# pocsagboardv2.net
KiCad netlist of a schematic drawn in EAGLE
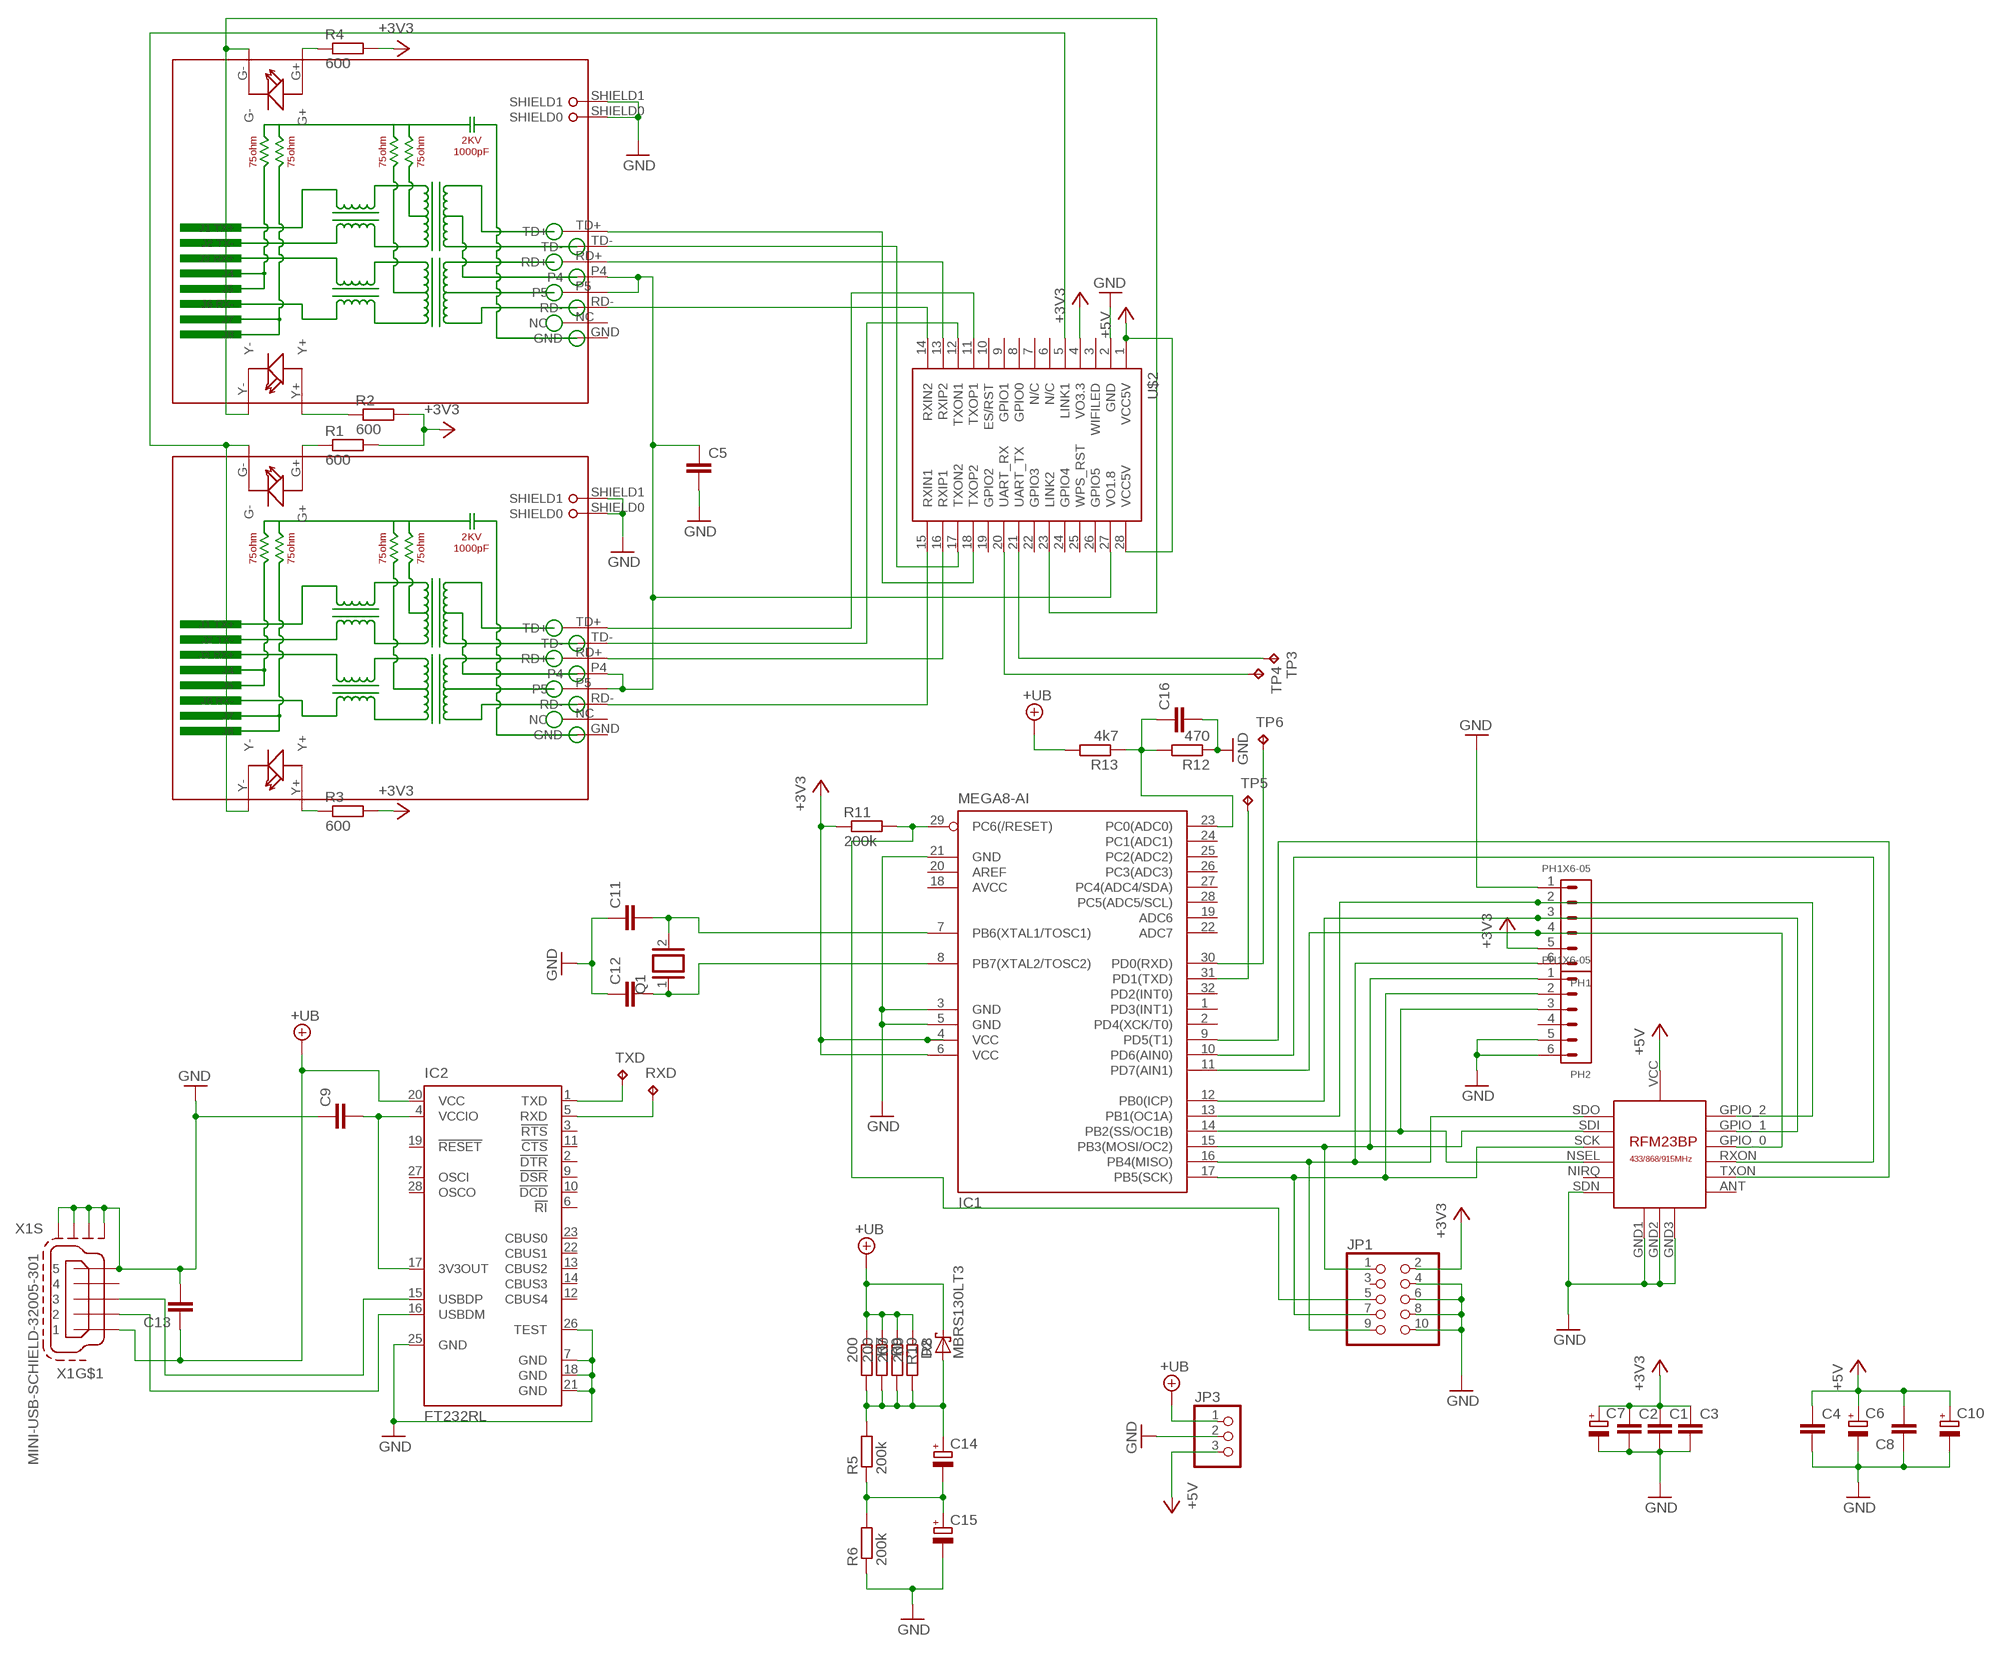
[diagram p0: schematic, sheet 1]

(export (version "E")
  (design (tool "Eeschema 10.0.6"))
  (components
    (comp (ref "C1")
      (value "C-EUC1206K")
      (footprint "eagle-import:C1206K")
      (libsource (lib "eagle-import") (part "C-EUC1206K"))
    )
    (comp (ref "C2")
      (value "C-EUC1206K")
      (footprint "eagle-import:C1206K")
      (libsource (lib "eagle-import") (part "C-EUC1206K"))
    )
    (comp (ref "C3")
      (value "C-EUC1206K")
      (footprint "eagle-import:C1206K")
      (libsource (lib "eagle-import") (part "C-EUC1206K"))
    )
    (comp (ref "C4")
      (value "C-EUC1206K")
      (footprint "eagle-import:C1206K")
      (libsource (lib "eagle-import") (part "C-EUC1206K"))
    )
    (comp (ref "C5")
      (value "C-EUC1206K")
      (footprint "eagle-import:C1206K")
      (libsource (lib "eagle-import") (part "C-EUC1206K"))
    )
    (comp (ref "C6")
      (value "CPOL-EU175TMP-0808")
      (footprint "eagle-import:175TMP-0808")
      (libsource (lib "eagle-import") (part "CPOL-EU175TMP-0808"))
    )
    (comp (ref "C7")
      (value "CPOL-EU175TMP-0808")
      (footprint "eagle-import:175TMP-0808")
      (libsource (lib "eagle-import") (part "CPOL-EU175TMP-0808"))
    )
    (comp (ref "C8")
      (value "C-EUC1206K")
      (footprint "eagle-import:C1206K")
      (libsource (lib "eagle-import") (part "C-EUC1206K"))
    )
    (comp (ref "C9")
      (value "C-EUC1206K")
      (footprint "eagle-import:C1206K")
      (libsource (lib "eagle-import") (part "C-EUC1206K"))
    )
    (comp (ref "C10")
      (value "CPOL-EU175TMP-0808")
      (footprint "eagle-import:175TMP-0808")
      (libsource (lib "eagle-import") (part "CPOL-EU175TMP-0808"))
    )
    (comp (ref "C11")
      (value "C-EUC0805")
      (footprint "eagle-import:C0805")
      (libsource (lib "eagle-import") (part "C-EUC0805"))
    )
    (comp (ref "C12")
      (value "C-EUC0805")
      (footprint "eagle-import:C0805")
      (libsource (lib "eagle-import") (part "C-EUC0805"))
    )
    (comp (ref "C13")
      (value "C-EUC1206K")
      (footprint "eagle-import:C1206K")
      (libsource (lib "eagle-import") (part "C-EUC1206K"))
    )
    (comp (ref "C14")
      (value "CPOL-EUSANYO_F")
      (footprint "eagle-import:SANYO-OSCON_F")
      (libsource (lib "eagle-import") (part "CPOL-EUSANYO_F"))
    )
    (comp (ref "C15")
      (value "CPOL-EUSANYO_F")
      (footprint "eagle-import:SANYO-OSCON_F")
      (libsource (lib "eagle-import") (part "CPOL-EUSANYO_F"))
    )
    (comp (ref "C16")
      (value "C-EUC1206K")
      (footprint "eagle-import:C1206K")
      (libsource (lib "eagle-import") (part "C-EUC1206K"))
    )
    (comp (ref "D2")
      (value "MBRS130LT3")
      (footprint "eagle-import:SMB")
      (libsource (lib "eagle-import") (part "MBRS130LT3"))
    )
    (comp (ref "IC1")
      (value "MEGA8-AI")
      (footprint "eagle-import:TQFP32-08")
      (fields (field (name "MPN") "ATMEGA8-16AU"))
      (libsource (lib "eagle-import") (part "MEGA8-AI"))
    )
    (comp (ref "IC2")
      (value "FT232RL")
      (footprint "eagle-import:SSOP28")
      (libsource (lib "eagle-import") (part "FT232RL"))
    )
    (comp (ref "JP1")
      (value "PINHD-2X5")
      (footprint "eagle-import:2X05")
      (libsource (lib "eagle-import") (part "PINHD-2X5"))
    )
    (comp (ref "JP3")
      (value "PINHD-1X3")
      (footprint "eagle-import:1X03")
      (libsource (lib "eagle-import") (part "PINHD-1X3"))
    )
    (comp (ref "PH1")
      (value "PH1X6-05")
      (footprint "eagle-import:PH005-1-6")
      (libsource (lib "eagle-import") (part "PH1X6-05"))
    )
    (comp (ref "PH2")
      (value "PH1X6-05")
      (footprint "eagle-import:PH005-1-6")
      (libsource (lib "eagle-import") (part "PH1X6-05"))
    )
    (comp (ref "Q1")
      (value "XTAL/S")
      (footprint "eagle-import:QS")
      (libsource (lib "eagle-import") (part "XTAL/S"))
    )
    (comp (ref "R1")
      (value "600")
      (footprint "eagle-import:M1206")
      (libsource (lib "eagle-import") (part "R-EU_M1206"))
    )
    (comp (ref "R2")
      (value "600")
      (footprint "eagle-import:M1206")
      (libsource (lib "eagle-import") (part "R-EU_M1206"))
    )
    (comp (ref "R3")
      (value "600")
      (footprint "eagle-import:M1206")
      (libsource (lib "eagle-import") (part "R-EU_M1206"))
    )
    (comp (ref "R4")
      (value "600")
      (footprint "eagle-import:M1206")
      (libsource (lib "eagle-import") (part "R-EU_M1206"))
    )
    (comp (ref "R5")
      (value "200k")
      (footprint "eagle-import:R1206")
      (libsource (lib "eagle-import") (part "R-EU_R1206"))
    )
    (comp (ref "R6")
      (value "200k")
      (footprint "eagle-import:R1206")
      (libsource (lib "eagle-import") (part "R-EU_R1206"))
    )
    (comp (ref "R7")
      (value "200")
      (footprint "eagle-import:R1206")
      (libsource (lib "eagle-import") (part "R-EU_R1206"))
    )
    (comp (ref "R8")
      (value "200")
      (footprint "eagle-import:R1206")
      (libsource (lib "eagle-import") (part "R-EU_R1206"))
    )
    (comp (ref "R9")
      (value "200")
      (footprint "eagle-import:R1206")
      (libsource (lib "eagle-import") (part "R-EU_R1206"))
    )
    (comp (ref "R10")
      (value "200")
      (footprint "eagle-import:R1206")
      (libsource (lib "eagle-import") (part "R-EU_R1206"))
    )
    (comp (ref "R11")
      (value "200k")
      (footprint "eagle-import:R1206")
      (libsource (lib "eagle-import") (part "R-EU_R1206"))
    )
    (comp (ref "R12")
      (value "470")
      (footprint "eagle-import:R1206")
      (libsource (lib "eagle-import") (part "R-EU_R1206"))
    )
    (comp (ref "R13")
      (value "4k7")
      (footprint "eagle-import:R1206")
      (libsource (lib "eagle-import") (part "R-EU_R1206"))
    )
    (comp (ref "RJ1")
      (value "HR911105A")
      (footprint "eagle-import:HR911105A")
      (libsource (lib "eagle-import") (part "HR911105A"))
    )
    (comp (ref "RJ2")
      (value "HR911105A")
      (footprint "eagle-import:HR911105A")
      (libsource (lib "eagle-import") (part "HR911105A"))
    )
    (comp (ref "RXD")
      (value "TPTP10SQ")
      (footprint "eagle-import:TP10SQ")
      (libsource (lib "eagle-import") (part "TPTP10SQ"))
    )
    (comp (ref "TP3")
      (value "TPTP10SQ")
      (footprint "eagle-import:TP10SQ")
      (libsource (lib "eagle-import") (part "TPTP10SQ"))
    )
    (comp (ref "TP4")
      (value "TPTP10SQ")
      (footprint "eagle-import:TP10SQ")
      (libsource (lib "eagle-import") (part "TPTP10SQ"))
    )
    (comp (ref "TP5")
      (value "TPTP10SQ")
      (footprint "eagle-import:TP10SQ")
      (libsource (lib "eagle-import") (part "TPTP10SQ"))
    )
    (comp (ref "TP6")
      (value "TPTP10SQ")
      (footprint "eagle-import:TP10SQ")
      (libsource (lib "eagle-import") (part "TPTP10SQ"))
    )
    (comp (ref "TXD")
      (value "TPTP10SQ")
      (footprint "eagle-import:TP10SQ")
      (libsource (lib "eagle-import") (part "TPTP10SQ"))
    )
    (comp (ref "U$1")
      (value "RFM23BP")
      (footprint "eagle-import:RFM23BP")
      (libsource (lib "eagle-import") (part "RFM23BP"))
    )
    (comp (ref "U$2")
      (value "HLK-RM04")
      (footprint "eagle-import:HLK-RM04")
      (libsource (lib "eagle-import") (part "HLK-RM04"))
    )
    (comp (ref "X1")
      (value "MINI-USB-SCHIELD-32005-301")
      (footprint "eagle-import:32005-301")
      (libsource (lib "eagle-import") (part "MINI-USB-SCHIELD-32005-301"))
    )
  )
  (nets
    (net (code "1") (name "+3V3") (class "Default")
      (node (ref "C1") (pin "1") (pinfunction "1_1") (pintype "passive"))
      (node (ref "C2") (pin "1") (pinfunction "1_1") (pintype "passive"))
      (node (ref "C3") (pin "1") (pinfunction "1_1") (pintype "passive"))
      (node (ref "C7") (pin "+") (pinfunction "+_+") (pintype "passive"))
      (node (ref "IC1") (pin "4") (pinfunction "VCC_4") (pintype "power_in"))
      (node (ref "IC1") (pin "6") (pinfunction "VCC_6") (pintype "power_in"))
      (node (ref "JP1") (pin "2") (pinfunction "2_2") (pintype "passive"))
      (node (ref "PH1") (pin "5") (pinfunction "5_5") (pintype "bidirectional"))
      (node (ref "R1") (pin "2") (pinfunction "2_2") (pintype "passive"))
      (node (ref "R11") (pin "1") (pinfunction "1_1") (pintype "passive"))
      (node (ref "R2") (pin "2") (pinfunction "2_2") (pintype "passive"))
      (node (ref "R3") (pin "2") (pinfunction "2_2") (pintype "passive"))
      (node (ref "R4") (pin "2") (pinfunction "2_2") (pintype "passive"))
      (node (ref "U$2") (pin "4") (pinfunction "VO3.3_4") (pintype "bidirectional"))
    )
    (net (code "2") (name "+5V") (class "Default")
      (node (ref "C10") (pin "+") (pinfunction "+_+") (pintype "passive"))
      (node (ref "C4") (pin "1") (pinfunction "1_1") (pintype "passive"))
      (node (ref "C6") (pin "+") (pinfunction "+_+") (pintype "passive"))
      (node (ref "C8") (pin "2") (pinfunction "2_2") (pintype "passive"))
      (node (ref "JP3") (pin "3") (pinfunction "3_3") (pintype "passive"))
      (node (ref "U$1") (pin "VCC") (pinfunction "VCC_VCC") (pintype "power_in"))
      (node (ref "U$2") (pin "1") (pinfunction "VCC5V_1") (pintype "bidirectional"))
      (node (ref "U$2") (pin "28") (pinfunction "VCC5V_28") (pintype "bidirectional"))
    )
    (net (code "3") (name "+UB") (class "Default")
      (node (ref "C13") (pin "1") (pinfunction "1_1") (pintype "passive"))
      (node (ref "D2") (pin "C") (pinfunction "C_C") (pintype "passive"))
      (node (ref "IC2") (pin "20") (pinfunction "VCC_20") (pintype "power_in"))
      (node (ref "JP3") (pin "1") (pinfunction "1_1") (pintype "passive"))
      (node (ref "R10") (pin "1") (pinfunction "1_1") (pintype "passive"))
      (node (ref "R13") (pin "2") (pinfunction "2_2") (pintype "passive"))
      (node (ref "R7") (pin "1") (pinfunction "1_1") (pintype "passive"))
      (node (ref "R8") (pin "1") (pinfunction "1_1") (pintype "passive"))
      (node (ref "R9") (pin "1") (pinfunction "1_1") (pintype "passive"))
      (node (ref "X1") (pin "1") (pinfunction "1_1") (pintype "passive"))
    )
    (net (code "4") (name "/AVCC") (class "Default")
      (node (ref "IC1") (pin "18") (pinfunction "AVCC_18") (pintype "power_in"))
    )
    (net (code "5") (name "GND") (class "Default")
      (node (ref "C1") (pin "2") (pinfunction "2_2") (pintype "passive"))
      (node (ref "C10") (pin "-") (pinfunction "-_-") (pintype "passive"))
      (node (ref "C11") (pin "1") (pinfunction "1_1") (pintype "passive"))
      (node (ref "C12") (pin "1") (pinfunction "1_1") (pintype "passive"))
      (node (ref "C13") (pin "2") (pinfunction "2_2") (pintype "passive"))
      (node (ref "C15") (pin "-") (pinfunction "-_-") (pintype "passive"))
      (node (ref "C16") (pin "2") (pinfunction "2_2") (pintype "passive"))
      (node (ref "C2") (pin "2") (pinfunction "2_2") (pintype "passive"))
      (node (ref "C3") (pin "2") (pinfunction "2_2") (pintype "passive"))
      (node (ref "C4") (pin "2") (pinfunction "2_2") (pintype "passive"))
      (node (ref "C5") (pin "2") (pinfunction "2_2") (pintype "passive"))
      (node (ref "C6") (pin "-") (pinfunction "-_-") (pintype "passive"))
      (node (ref "C7") (pin "-") (pinfunction "-_-") (pintype "passive"))
      (node (ref "C8") (pin "1") (pinfunction "1_1") (pintype "passive"))
      (node (ref "C9") (pin "1") (pinfunction "1_1") (pintype "passive"))
      (node (ref "IC1") (pin "21") (pinfunction "GND_21") (pintype "power_in"))
      (node (ref "IC1") (pin "3") (pinfunction "GND_3") (pintype "power_in"))
      (node (ref "IC1") (pin "5") (pinfunction "GND_5") (pintype "power_in"))
      (node (ref "IC2") (pin "18") (pinfunction "GND_18") (pintype "power_in"))
      (node (ref "IC2") (pin "21") (pinfunction "GND_21") (pintype "power_in"))
      (node (ref "IC2") (pin "25") (pinfunction "GND_25") (pintype "power_in"))
      (node (ref "IC2") (pin "26") (pinfunction "TEST_26") (pintype "input"))
      (node (ref "IC2") (pin "7") (pinfunction "GND_7") (pintype "power_in"))
      (node (ref "JP1") (pin "10") (pinfunction "10_10") (pintype "passive"))
      (node (ref "JP1") (pin "4") (pinfunction "4_4") (pintype "passive"))
      (node (ref "JP1") (pin "6") (pinfunction "6_6") (pintype "passive"))
      (node (ref "JP1") (pin "8") (pinfunction "8_8") (pintype "passive"))
      (node (ref "JP3") (pin "2") (pinfunction "2_2") (pintype "passive"))
      (node (ref "PH1") (pin "1") (pinfunction "1_1") (pintype "bidirectional"))
      (node (ref "PH2") (pin "5") (pinfunction "5_5") (pintype "bidirectional"))
      (node (ref "PH2") (pin "6") (pinfunction "6_6") (pintype "bidirectional"))
      (node (ref "R12") (pin "1") (pinfunction "1_1") (pintype "passive"))
      (node (ref "R6") (pin "1") (pinfunction "1_1") (pintype "passive"))
      (node (ref "RJ1") (pin "SHIELD0") (pinfunction "SHIELD0_SHIELD0") (pintype "bidirectional"))
      (node (ref "RJ1") (pin "SHIELD1") (pinfunction "SHIELD1_SHIELD1") (pintype "bidirectional"))
      (node (ref "RJ2") (pin "SHIELD0") (pinfunction "SHIELD0_SHIELD0") (pintype "bidirectional"))
      (node (ref "RJ2") (pin "SHIELD1") (pinfunction "SHIELD1_SHIELD1") (pintype "bidirectional"))
      (node (ref "U$1") (pin "GND1") (pinfunction "GND1_GND1") (pintype "power_in"))
      (node (ref "U$1") (pin "GND2") (pinfunction "GND2_GND2") (pintype "power_in"))
      (node (ref "U$1") (pin "GND3") (pinfunction "GND3_GND3") (pintype "power_in"))
      (node (ref "U$1") (pin "SDN") (pinfunction "SDN_SDN") (pintype "bidirectional"))
      (node (ref "U$2") (pin "2") (pinfunction "GND_2") (pintype "bidirectional"))
      (node (ref "X1") (pin "5") (pinfunction "5_5") (pintype "passive"))
      (node (ref "X1") (pin "M1") (pinfunction "S1_M1") (pintype "passive"))
      (node (ref "X1") (pin "M2") (pinfunction "S2_M2") (pintype "passive"))
      (node (ref "X1") (pin "M3") (pinfunction "S3_M3") (pintype "passive"))
      (node (ref "X1") (pin "M4") (pinfunction "S4_M4") (pintype "passive"))
    )
    (net (code "6") (name "Net-(C14-Pad+)") (class "Default")
      (node (ref "C14") (pin "+") (pinfunction "+_+") (pintype "passive"))
      (node (ref "D2") (pin "A") (pinfunction "A_A") (pintype "passive"))
      (node (ref "R10") (pin "2") (pinfunction "2_2") (pintype "passive"))
      (node (ref "R5") (pin "2") (pinfunction "2_2") (pintype "passive"))
      (node (ref "R7") (pin "2") (pinfunction "2_2") (pintype "passive"))
      (node (ref "R8") (pin "2") (pinfunction "2_2") (pintype "passive"))
      (node (ref "R9") (pin "2") (pinfunction "2_2") (pintype "passive"))
    )
    (net (code "7") (name "Net-(C14-Pad-)") (class "Default")
      (node (ref "C14") (pin "-") (pinfunction "-_-") (pintype "passive"))
      (node (ref "C15") (pin "+") (pinfunction "+_+") (pintype "passive"))
      (node (ref "R5") (pin "1") (pinfunction "1_1") (pintype "passive"))
      (node (ref "R6") (pin "2") (pinfunction "2_2") (pintype "passive"))
    )
    (net (code "8") (name "Net-(IC1-PB0(ICP))") (class "Default")
      (node (ref "IC1") (pin "12") (pinfunction "PB0(ICP)_12") (pintype "bidirectional"))
      (node (ref "PH1") (pin "3") (pinfunction "3_3") (pintype "bidirectional"))
      (node (ref "U$1") (pin "GPIO_1") (pinfunction "GPIO_1_GPIO_1") (pintype "bidirectional"))
    )
    (net (code "9") (name "Net-(IC1-PB1(OC1A))") (class "Default")
      (node (ref "IC1") (pin "13") (pinfunction "PB1(OC1A)_13") (pintype "bidirectional"))
      (node (ref "PH1") (pin "2") (pinfunction "2_2") (pintype "bidirectional"))
      (node (ref "U$1") (pin "GPIO_2") (pinfunction "GPIO_2_GPIO_2") (pintype "bidirectional"))
    )
    (net (code "10") (name "Net-(IC1-PB2(SS{slash}OC1B))") (class "Default")
      (node (ref "IC1") (pin "14") (pinfunction "PB2(SS/OC1B)_14") (pintype "bidirectional"))
      (node (ref "PH2") (pin "3") (pinfunction "3_3") (pintype "bidirectional"))
      (node (ref "U$1") (pin "NSEL") (pinfunction "NSEL_NSEL") (pintype "bidirectional"))
    )
    (net (code "11") (name "Net-(IC1-PB3(MOSI{slash}OC2))") (class "Default")
      (node (ref "IC1") (pin "15") (pinfunction "PB3(MOSI/OC2)_15") (pintype "bidirectional"))
      (node (ref "JP1") (pin "1") (pinfunction "1_1") (pintype "passive"))
      (node (ref "PH2") (pin "1") (pinfunction "1_1") (pintype "bidirectional"))
      (node (ref "U$1") (pin "SDI") (pinfunction "SDI_SDI") (pintype "bidirectional"))
    )
    (net (code "12") (name "Net-(IC1-PB4(MISO))") (class "Default")
      (node (ref "IC1") (pin "16") (pinfunction "PB4(MISO)_16") (pintype "bidirectional"))
      (node (ref "JP1") (pin "9") (pinfunction "9_9") (pintype "passive"))
      (node (ref "PH1") (pin "6") (pinfunction "6_6") (pintype "bidirectional"))
      (node (ref "U$1") (pin "SDO") (pinfunction "SDO_SDO") (pintype "bidirectional"))
    )
    (net (code "13") (name "Net-(IC1-PB5(SCK))") (class "Default")
      (node (ref "IC1") (pin "17") (pinfunction "PB5(SCK)_17") (pintype "bidirectional"))
      (node (ref "JP1") (pin "7") (pinfunction "7_7") (pintype "passive"))
      (node (ref "PH2") (pin "2") (pinfunction "2_2") (pintype "bidirectional"))
      (node (ref "U$1") (pin "SCK") (pinfunction "SCK_SCK") (pintype "bidirectional"))
    )
    (net (code "14") (name "Net-(IC1-PB6(XTAL1{slash}TOSC1))") (class "Default")
      (node (ref "C11") (pin "2") (pinfunction "2_2") (pintype "passive"))
      (node (ref "IC1") (pin "7") (pinfunction "PB6(XTAL1/TOSC1)_7") (pintype "bidirectional"))
      (node (ref "Q1") (pin "2") (pinfunction "2_2") (pintype "passive"))
    )
    (net (code "15") (name "Net-(IC1-PB7(XTAL2{slash}TOSC2))") (class "Default")
      (node (ref "C12") (pin "2") (pinfunction "2_2") (pintype "passive"))
      (node (ref "IC1") (pin "8") (pinfunction "PB7(XTAL2/TOSC2)_8") (pintype "bidirectional"))
      (node (ref "Q1") (pin "1") (pinfunction "1_1") (pintype "passive"))
    )
    (net (code "16") (name "Net-(IC1-PC0(ADC0))") (class "Default")
      (node (ref "C16") (pin "1") (pinfunction "1_1") (pintype "passive"))
      (node (ref "IC1") (pin "23") (pinfunction "PC0(ADC0)_23") (pintype "bidirectional"))
      (node (ref "R12") (pin "2") (pinfunction "2_2") (pintype "passive"))
      (node (ref "R13") (pin "1") (pinfunction "1_1") (pintype "passive"))
    )
    (net (code "17") (name "Net-(IC1-PC6({slash}RESET))") (class "Default")
      (node (ref "IC1") (pin "29") (pinfunction "PC6(/RESET)_29") (pintype "bidirectional"))
      (node (ref "JP1") (pin "5") (pinfunction "5_5") (pintype "passive"))
      (node (ref "R11") (pin "2") (pinfunction "2_2") (pintype "passive"))
    )
    (net (code "18") (name "Net-(IC1-PD0(RXD))") (class "Default")
      (node (ref "IC1") (pin "30") (pinfunction "PD0(RXD)_30") (pintype "bidirectional"))
      (node (ref "TP6") (pin "TP") (pinfunction "TP_TP") (pintype "input"))
    )
    (net (code "19") (name "Net-(IC1-PD1(TXD))") (class "Default")
      (node (ref "IC1") (pin "31") (pinfunction "PD1(TXD)_31") (pintype "bidirectional"))
      (node (ref "TP5") (pin "TP") (pinfunction "TP_TP") (pintype "input"))
    )
    (net (code "20") (name "Net-(IC1-PD5(T1))") (class "Default")
      (node (ref "IC1") (pin "9") (pinfunction "PD5(T1)_9") (pintype "bidirectional"))
      (node (ref "U$1") (pin "TXON") (pinfunction "TXON_TXON") (pintype "bidirectional"))
    )
    (net (code "21") (name "Net-(IC1-PD6(AIN0))") (class "Default")
      (node (ref "IC1") (pin "10") (pinfunction "PD6(AIN0)_10") (pintype "bidirectional"))
      (node (ref "U$1") (pin "RXON") (pinfunction "RXON_RXON") (pintype "bidirectional"))
    )
    (net (code "22") (name "Net-(IC1-PD7(AIN1))") (class "Default")
      (node (ref "IC1") (pin "11") (pinfunction "PD7(AIN1)_11") (pintype "bidirectional"))
      (node (ref "PH1") (pin "4") (pinfunction "4_4") (pintype "bidirectional"))
      (node (ref "U$1") (pin "GPIO_0") (pinfunction "GPIO_0_GPIO_0") (pintype "bidirectional"))
    )
    (net (code "23") (name "Net-(IC2-3V3OUT)") (class "Default")
      (node (ref "C9") (pin "2") (pinfunction "2_2") (pintype "passive"))
      (node (ref "IC2") (pin "17") (pinfunction "3V3OUT_17") (pintype "output"))
      (node (ref "IC2") (pin "4") (pinfunction "VCCIO_4") (pintype "power_in"))
    )
    (net (code "24") (name "Net-(IC2-RXD)") (class "Default")
      (node (ref "IC2") (pin "5") (pinfunction "RXD_5") (pintype "input"))
      (node (ref "RXD") (pin "TP") (pinfunction "TP_TP") (pintype "input"))
    )
    (net (code "25") (name "Net-(IC2-TXD)") (class "Default")
      (node (ref "IC2") (pin "1") (pinfunction "TXD_1") (pintype "output"))
      (node (ref "TXD") (pin "TP") (pinfunction "TP_TP") (pintype "input"))
    )
    (net (code "26") (name "Net-(IC2-USBDM)") (class "Default")
      (node (ref "IC2") (pin "16") (pinfunction "USBDM_16") (pintype "bidirectional"))
      (node (ref "X1") (pin "2") (pinfunction "2_2") (pintype "passive"))
    )
    (net (code "27") (name "Net-(IC2-USBDP)") (class "Default")
      (node (ref "IC2") (pin "15") (pinfunction "USBDP_15") (pintype "bidirectional"))
      (node (ref "X1") (pin "3") (pinfunction "3_3") (pintype "passive"))
    )
    (net (code "28") (name "Net-(R1-Pad1)") (class "Default")
      (node (ref "R1") (pin "1") (pinfunction "1_1") (pintype "passive"))
      (node (ref "RJ1") (pin "G+") (pinfunction "G+_G+") (pintype "bidirectional"))
    )
    (net (code "29") (name "Net-(R2-Pad1)") (class "Default")
      (node (ref "R2") (pin "1") (pinfunction "1_1") (pintype "passive"))
      (node (ref "RJ2") (pin "Y+") (pinfunction "Y+_Y+") (pintype "bidirectional"))
    )
    (net (code "30") (name "Net-(R3-Pad1)") (class "Default")
      (node (ref "R3") (pin "1") (pinfunction "1_1") (pintype "passive"))
      (node (ref "RJ1") (pin "Y+") (pinfunction "Y+_Y+") (pintype "bidirectional"))
    )
    (net (code "31") (name "Net-(R4-Pad1)") (class "Default")
      (node (ref "R4") (pin "1") (pinfunction "1_1") (pintype "passive"))
      (node (ref "RJ2") (pin "G+") (pinfunction "G+_G+") (pintype "bidirectional"))
    )
    (net (code "32") (name "Net-(U$2-LINK1)") (class "Default")
      (node (ref "RJ1") (pin "G-") (pinfunction "G-_G-") (pintype "bidirectional"))
      (node (ref "RJ1") (pin "Y-") (pinfunction "Y-_Y-") (pintype "bidirectional"))
      (node (ref "U$2") (pin "5") (pinfunction "LINK1_5") (pintype "bidirectional"))
    )
    (net (code "33") (name "Net-(U$2-LINK2)") (class "Default")
      (node (ref "RJ2") (pin "G-") (pinfunction "G-_G-") (pintype "bidirectional"))
      (node (ref "RJ2") (pin "Y-") (pinfunction "Y-_Y-") (pintype "bidirectional"))
      (node (ref "U$2") (pin "23") (pinfunction "LINK2_23") (pintype "bidirectional"))
    )
    (net (code "34") (name "Net-(U$2-RXIN1)") (class "Default")
      (node (ref "RJ1") (pin "RD-") (pinfunction "RD-_RD-") (pintype "bidirectional"))
      (node (ref "U$2") (pin "15") (pinfunction "RXIN1_15") (pintype "bidirectional"))
    )
    (net (code "35") (name "Net-(U$2-RXIN2)") (class "Default")
      (node (ref "RJ2") (pin "RD-") (pinfunction "RD-_RD-") (pintype "bidirectional"))
      (node (ref "U$2") (pin "14") (pinfunction "RXIN2_14") (pintype "bidirectional"))
    )
    (net (code "36") (name "Net-(U$2-RXIP1)") (class "Default")
      (node (ref "RJ1") (pin "RD+") (pinfunction "RD+_RD+") (pintype "bidirectional"))
      (node (ref "U$2") (pin "16") (pinfunction "RXIP1_16") (pintype "bidirectional"))
    )
    (net (code "37") (name "Net-(U$2-RXIP2)") (class "Default")
      (node (ref "RJ2") (pin "RD+") (pinfunction "RD+_RD+") (pintype "bidirectional"))
      (node (ref "U$2") (pin "13") (pinfunction "RXIP2_13") (pintype "bidirectional"))
    )
    (net (code "38") (name "Net-(U$2-TXON1)") (class "Default")
      (node (ref "RJ1") (pin "TD-") (pinfunction "TD-_TD-") (pintype "bidirectional"))
      (node (ref "U$2") (pin "12") (pinfunction "TXON1_12") (pintype "bidirectional"))
    )
    (net (code "39") (name "Net-(U$2-TXON2)") (class "Default")
      (node (ref "RJ2") (pin "TD-") (pinfunction "TD-_TD-") (pintype "bidirectional"))
      (node (ref "U$2") (pin "17") (pinfunction "TXON2_17") (pintype "bidirectional"))
    )
    (net (code "40") (name "Net-(U$2-TXOP1)") (class "Default")
      (node (ref "RJ1") (pin "TD+") (pinfunction "TD+_TD+") (pintype "bidirectional"))
      (node (ref "U$2") (pin "11") (pinfunction "TXOP1_11") (pintype "bidirectional"))
    )
    (net (code "41") (name "Net-(U$2-TXOP2)") (class "Default")
      (node (ref "RJ2") (pin "TD+") (pinfunction "TD+_TD+") (pintype "bidirectional"))
      (node (ref "U$2") (pin "18") (pinfunction "TXOP2_18") (pintype "bidirectional"))
    )
    (net (code "42") (name "Net-(U$2-UART_RX)") (class "Default")
      (node (ref "TP4") (pin "TP") (pinfunction "TP_TP") (pintype "input"))
      (node (ref "U$2") (pin "20") (pinfunction "UART_RX_20") (pintype "bidirectional"))
    )
    (net (code "43") (name "Net-(U$2-UART_TX)") (class "Default")
      (node (ref "TP3") (pin "TP") (pinfunction "TP_TP") (pintype "input"))
      (node (ref "U$2") (pin "21") (pinfunction "UART_TX_21") (pintype "bidirectional"))
    )
    (net (code "44") (name "Net-(U$2-VO1.8)") (class "Default")
      (node (ref "C5") (pin "1") (pinfunction "1_1") (pintype "passive"))
      (node (ref "RJ1") (pin "P4") (pinfunction "P4_P4") (pintype "bidirectional"))
      (node (ref "RJ1") (pin "P5") (pinfunction "P5_P5") (pintype "bidirectional"))
      (node (ref "RJ2") (pin "P4") (pinfunction "P4_P4") (pintype "bidirectional"))
      (node (ref "RJ2") (pin "P5") (pinfunction "P5_P5") (pintype "bidirectional"))
      (node (ref "U$2") (pin "27") (pinfunction "VO1.8_27") (pintype "bidirectional"))
    )
    (net (code "45") (name "unconnected-(IC1-ADC6-Pad19)") (class "Default")
      (node (ref "IC1") (pin "19") (pinfunction "ADC6_19") (pintype "bidirectional"))
    )
    (net (code "46") (name "unconnected-(IC1-ADC7-Pad22)") (class "Default")
      (node (ref "IC1") (pin "22") (pinfunction "ADC7_22") (pintype "bidirectional"))
    )
    (net (code "47") (name "unconnected-(IC1-AREF-Pad20)") (class "Default")
      (node (ref "IC1") (pin "20") (pinfunction "AREF_20") (pintype "passive"))
    )
    (net (code "48") (name "unconnected-(IC1-PC1(ADC1)-Pad24)") (class "Default")
      (node (ref "IC1") (pin "24") (pinfunction "PC1(ADC1)_24") (pintype "bidirectional"))
    )
    (net (code "49") (name "unconnected-(IC1-PC2(ADC2)-Pad25)") (class "Default")
      (node (ref "IC1") (pin "25") (pinfunction "PC2(ADC2)_25") (pintype "bidirectional"))
    )
    (net (code "50") (name "unconnected-(IC1-PC3(ADC3)-Pad26)") (class "Default")
      (node (ref "IC1") (pin "26") (pinfunction "PC3(ADC3)_26") (pintype "bidirectional"))
    )
    (net (code "51") (name "unconnected-(IC1-PC4(ADC4{slash}SDA)-Pad27)") (class "Default")
      (node (ref "IC1") (pin "27") (pinfunction "PC4(ADC4/SDA)_27") (pintype "bidirectional"))
    )
    (net (code "52") (name "unconnected-(IC1-PC5(ADC5{slash}SCL)-Pad28)") (class "Default")
      (node (ref "IC1") (pin "28") (pinfunction "PC5(ADC5/SCL)_28") (pintype "bidirectional"))
    )
    (net (code "53") (name "unconnected-(IC1-PD2(INT0)-Pad32)") (class "Default")
      (node (ref "IC1") (pin "32") (pinfunction "PD2(INT0)_32") (pintype "bidirectional"))
    )
    (net (code "54") (name "unconnected-(IC1-PD3(INT1)-Pad1)") (class "Default")
      (node (ref "IC1") (pin "1") (pinfunction "PD3(INT1)_1") (pintype "bidirectional"))
    )
    (net (code "55") (name "unconnected-(IC1-PD4(XCK{slash}T0)-Pad2)") (class "Default")
      (node (ref "IC1") (pin "2") (pinfunction "PD4(XCK/T0)_2") (pintype "bidirectional"))
    )
    (net (code "56") (name "unconnected-(IC2-CBUS0-Pad23)") (class "Default")
      (node (ref "IC2") (pin "23") (pinfunction "CBUS0_23") (pintype "bidirectional"))
    )
    (net (code "57") (name "unconnected-(IC2-CBUS1-Pad22)") (class "Default")
      (node (ref "IC2") (pin "22") (pinfunction "CBUS1_22") (pintype "bidirectional"))
    )
    (net (code "58") (name "unconnected-(IC2-CBUS2-Pad13)") (class "Default")
      (node (ref "IC2") (pin "13") (pinfunction "CBUS2_13") (pintype "bidirectional"))
    )
    (net (code "59") (name "unconnected-(IC2-CBUS3-Pad14)") (class "Default")
      (node (ref "IC2") (pin "14") (pinfunction "CBUS3_14") (pintype "bidirectional"))
    )
    (net (code "60") (name "unconnected-(IC2-CBUS4-Pad12)") (class "Default")
      (node (ref "IC2") (pin "12") (pinfunction "CBUS4_12") (pintype "bidirectional"))
    )
    (net (code "61") (name "unconnected-(IC2-OSCI-Pad27)") (class "Default")
      (node (ref "IC2") (pin "27") (pinfunction "OSCI_27") (pintype "input"))
    )
    (net (code "62") (name "unconnected-(IC2-OSCO-Pad28)") (class "Default")
      (node (ref "IC2") (pin "28") (pinfunction "OSCO_28") (pintype "output"))
    )
    (net (code "63") (name "unconnected-(IC2-~{CTS}-Pad11)") (class "Default")
      (node (ref "IC2") (pin "11") (pinfunction "~{CTS}_11") (pintype "input"))
    )
    (net (code "64") (name "unconnected-(IC2-~{DCD}-Pad10)") (class "Default")
      (node (ref "IC2") (pin "10") (pinfunction "~{DCD}_10") (pintype "input"))
    )
    (net (code "65") (name "unconnected-(IC2-~{DSR}-Pad9)") (class "Default")
      (node (ref "IC2") (pin "9") (pinfunction "~{DSR}_9") (pintype "input"))
    )
    (net (code "66") (name "unconnected-(IC2-~{DTR}-Pad2)") (class "Default")
      (node (ref "IC2") (pin "2") (pinfunction "~{DTR}_2") (pintype "output"))
    )
    (net (code "67") (name "unconnected-(IC2-~{RESET}-Pad19)") (class "Default")
      (node (ref "IC2") (pin "19") (pinfunction "~{RESET}_19") (pintype "input"))
    )
    (net (code "68") (name "unconnected-(IC2-~{RI}-Pad6)") (class "Default")
      (node (ref "IC2") (pin "6") (pinfunction "~{RI}_6") (pintype "input"))
    )
    (net (code "69") (name "unconnected-(IC2-~{RTS}-Pad3)") (class "Default")
      (node (ref "IC2") (pin "3") (pinfunction "~{RTS}_3") (pintype "output"))
    )
    (net (code "70") (name "unconnected-(JP1-Pad3)") (class "Default")
      (node (ref "JP1") (pin "3") (pinfunction "3_3") (pintype "passive"))
    )
    (net (code "71") (name "unconnected-(PH2-Pad4)") (class "Default")
      (node (ref "PH2") (pin "4") (pinfunction "4_4") (pintype "bidirectional"))
    )
    (net (code "72") (name "unconnected-(RJ1-PadGND)") (class "Default")
      (node (ref "RJ1") (pin "GND") (pinfunction "GND_GND") (pintype "bidirectional"))
    )
    (net (code "73") (name "unconnected-(RJ1-PadNC)") (class "Default")
      (node (ref "RJ1") (pin "NC") (pinfunction "NC_NC") (pintype "bidirectional"))
    )
    (net (code "74") (name "unconnected-(RJ2-PadGND)") (class "Default")
      (node (ref "RJ2") (pin "GND") (pinfunction "GND_GND") (pintype "bidirectional"))
    )
    (net (code "75") (name "unconnected-(RJ2-PadNC)") (class "Default")
      (node (ref "RJ2") (pin "NC") (pinfunction "NC_NC") (pintype "bidirectional"))
    )
    (net (code "76") (name "unconnected-(U$1-PadANT)") (class "Default")
      (node (ref "U$1") (pin "ANT") (pinfunction "ANT_ANT") (pintype "bidirectional"))
    )
    (net (code "77") (name "unconnected-(U$1-PadNIRQ)") (class "Default")
      (node (ref "U$1") (pin "NIRQ") (pinfunction "NIRQ_NIRQ") (pintype "bidirectional"))
    )
    (net (code "78") (name "unconnected-(U$2-ES{slash}RST-Pad10)") (class "Default")
      (node (ref "U$2") (pin "10") (pinfunction "ES/RST_10") (pintype "bidirectional"))
    )
    (net (code "79") (name "unconnected-(U$2-GPIO0-Pad8)") (class "Default")
      (node (ref "U$2") (pin "8") (pinfunction "GPIO0_8") (pintype "bidirectional"))
    )
    (net (code "80") (name "unconnected-(U$2-GPIO1-Pad9)") (class "Default")
      (node (ref "U$2") (pin "9") (pinfunction "GPIO1_9") (pintype "bidirectional"))
    )
    (net (code "81") (name "unconnected-(U$2-GPIO2-Pad19)") (class "Default")
      (node (ref "U$2") (pin "19") (pinfunction "GPIO2_19") (pintype "bidirectional"))
    )
    (net (code "82") (name "unconnected-(U$2-GPIO3-Pad22)") (class "Default")
      (node (ref "U$2") (pin "22") (pinfunction "GPIO3_22") (pintype "bidirectional"))
    )
    (net (code "83") (name "unconnected-(U$2-GPIO4-Pad24)") (class "Default")
      (node (ref "U$2") (pin "24") (pinfunction "GPIO4_24") (pintype "bidirectional"))
    )
    (net (code "84") (name "unconnected-(U$2-GPIO5-Pad26)") (class "Default")
      (node (ref "U$2") (pin "26") (pinfunction "GPIO5_26") (pintype "bidirectional"))
    )
    (net (code "85") (name "unconnected-(U$2-N{slash}C-Pad6)") (class "Default")
      (node (ref "U$2") (pin "6") (pinfunction "N/C_6") (pintype "bidirectional"))
    )
    (net (code "86") (name "unconnected-(U$2-N{slash}C-Pad7)") (class "Default")
      (node (ref "U$2") (pin "7") (pinfunction "N/C_7") (pintype "bidirectional"))
    )
    (net (code "87") (name "unconnected-(U$2-WIFILED-Pad3)") (class "Default")
      (node (ref "U$2") (pin "3") (pinfunction "WIFILED_3") (pintype "bidirectional"))
    )
    (net (code "88") (name "unconnected-(U$2-WPS_RST-Pad25)") (class "Default")
      (node (ref "U$2") (pin "25") (pinfunction "WPS_RST_25") (pintype "bidirectional"))
    )
    (net (code "89") (name "unconnected-(X1-Pad4)") (class "Default")
      (node (ref "X1") (pin "4") (pinfunction "4_4") (pintype "passive"))
    )
  )
)
